# SOT23_SOT323_Vert.net
KiCad netlist of a schematic drawn in EAGLE
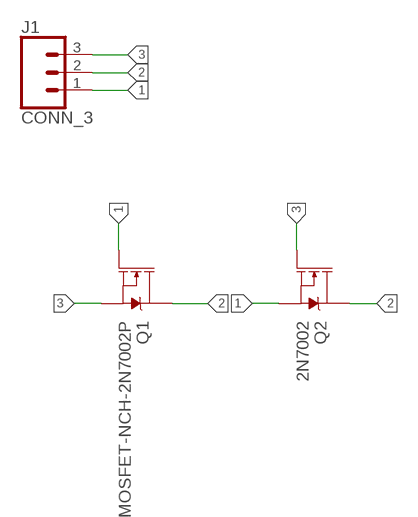
[diagram p0: schematic, sheet 1]

(export (version "E")
  (design (tool "Eeschema 10.0.6"))
  (components
    (comp (ref "J1")
      (value "CONN_3")
      (footprint "eagle-import:1X03")
      (libsource (lib "eagle-import") (part "CONN_3"))
    )
    (comp (ref "Q1")
      (value "MOSFET-NCH-2N7002P")
      (footprint "eagle-import:SOT23-3")
      (fields (field (name "MF") "Nexperia") (field (name "MPN") "2N7002P,215"))
      (libsource (lib "eagle-import") (part "MOSFET-NCH-2N7002P"))
    )
    (comp (ref "Q2")
      (value "2N7002")
      (footprint "eagle-import:SOT323")
      (fields (field (name "MF") "Diodes Incorporated") (field (name "MPN") "2N7002W-7-F"))
      (libsource (lib "eagle-import") (part "MOSFET-NCH-2N7002PW"))
    )
  )
  (nets
    (net (code "1") (name "1") (class "Default")
      (node (ref "J1") (pin "1") (pinfunction "1_1") (pintype "passive"))
      (node (ref "Q1") (pin "1") (pinfunction "G_1") (pintype "bidirectional"))
      (node (ref "Q2") (pin "2") (pinfunction "S_2") (pintype "bidirectional"))
    )
    (net (code "2") (name "2") (class "Default")
      (node (ref "J1") (pin "2") (pinfunction "2_2") (pintype "passive"))
      (node (ref "Q1") (pin "3") (pinfunction "D_3") (pintype "bidirectional"))
      (node (ref "Q2") (pin "3") (pinfunction "D_3") (pintype "bidirectional"))
    )
    (net (code "3") (name "3") (class "Default")
      (node (ref "J1") (pin "3") (pinfunction "3_3") (pintype "passive"))
      (node (ref "Q1") (pin "2") (pinfunction "S_2") (pintype "bidirectional"))
      (node (ref "Q2") (pin "1") (pinfunction "G_1") (pintype "bidirectional"))
    )
  )
)
